# SCH_Satlla_4_Main_Board_2023-01-26.net
KiCad netlist of a schematic drawn in EasyEDA
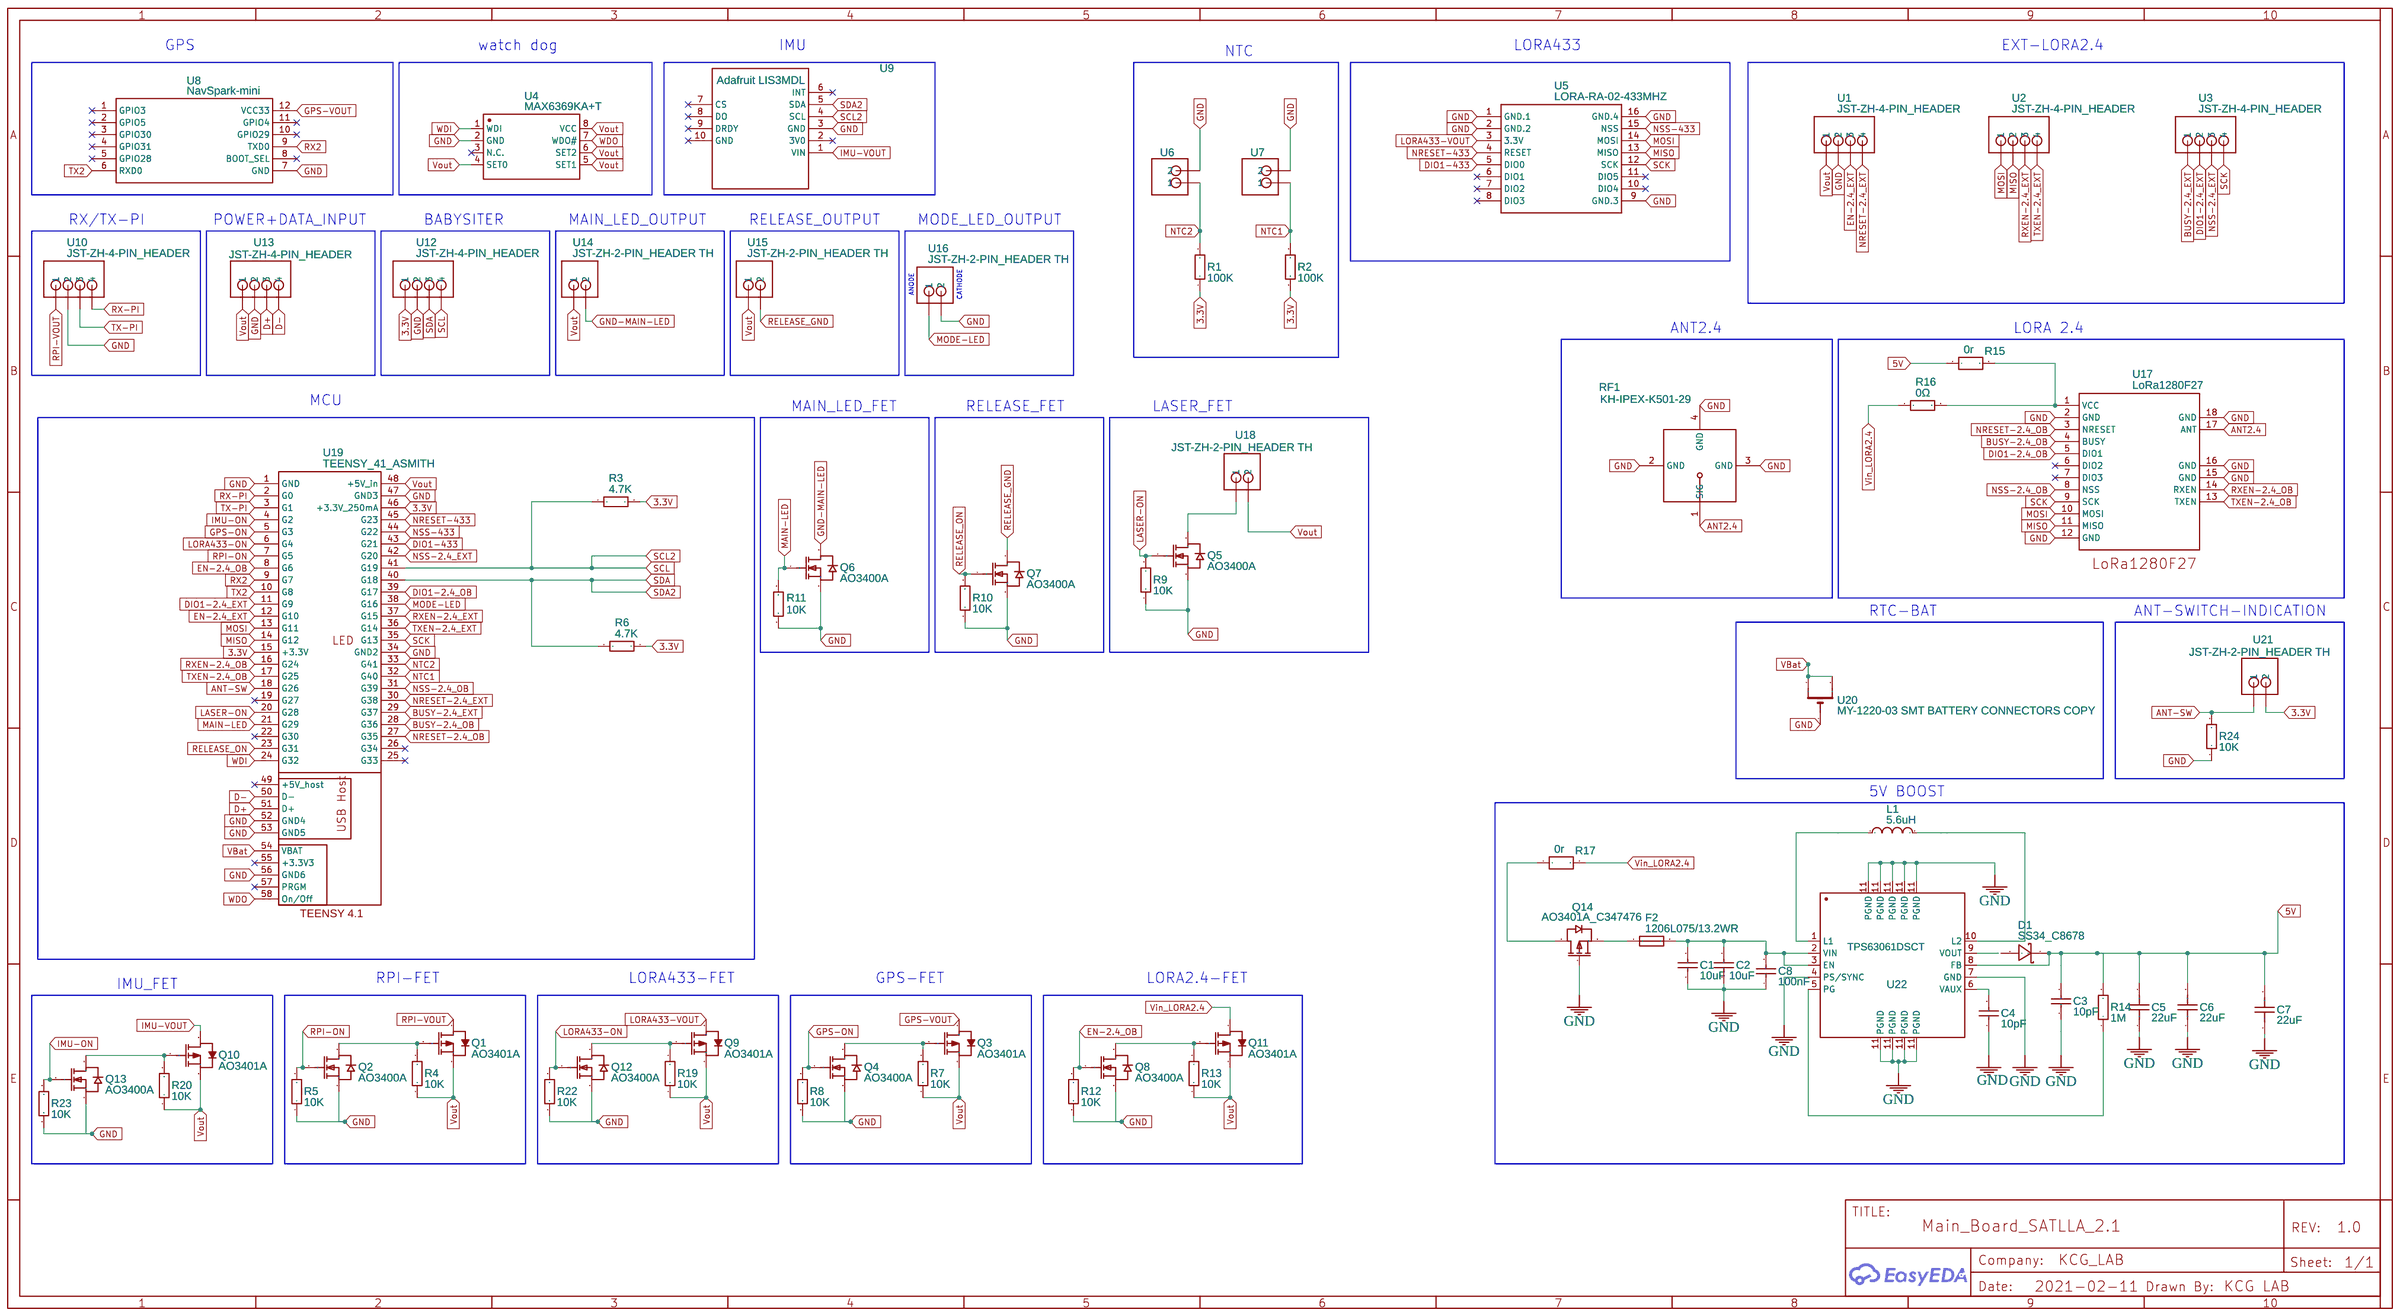
[diagram p0: schematic sheet]

(export (version "E")
  (design (tool "Eeschema 10.0.6"))
  (components
    (comp (ref "C1")
      (value "10uF")
      (fields
        (field (name "BOM_Manufacturer Part") "GRM188R61C106MA73D")
        (field (name "BOM_Supplier Part") "C86277")
      )
      (libsource (lib "") (part "GRM188R61C106MA73D"))
    )
    (comp (ref "C2")
      (value "10uF")
      (fields
        (field (name "BOM_Manufacturer Part") "GRM188R61C106MA73D")
        (field (name "BOM_Supplier Part") "C86277")
      )
      (libsource (lib "") (part "GRM188R61C106MA73D"))
    )
    (comp (ref "C3")
      (value "10pF")
      (fields
        (field (name "BOM_Manufacturer Part") "0603CG100J101NT")
        (field (name "BOM_Supplier Part") "C56033")
      )
      (libsource (lib "") (part "0603CG100J101NT"))
    )
    (comp (ref "C4")
      (value "10pF")
      (fields
        (field (name "BOM_Manufacturer Part") "0603CG100J101NT")
        (field (name "BOM_Supplier Part") "C56033")
      )
      (libsource (lib "") (part "0603CG100J101NT"))
    )
    (comp (ref "C5")
      (value "22uF")
      (fields
        (field (name "BOM_Manufacturer Part") "GRM219R61C226ME15L")
        (field (name "BOM_Supplier Part") "C162295")
      )
      (libsource (lib "") (part "GRM219R61C226ME15L"))
    )
    (comp (ref "C6")
      (value "22uF")
      (fields
        (field (name "BOM_Manufacturer Part") "GRM219R61C226ME15L")
        (field (name "BOM_Supplier Part") "C162295")
      )
      (libsource (lib "") (part "GRM219R61C226ME15L"))
    )
    (comp (ref "C7")
      (value "22uF")
      (fields
        (field (name "BOM_Manufacturer Part") "GRM219R61C226ME15L")
        (field (name "BOM_Supplier Part") "C162295")
      )
      (libsource (lib "") (part "GRM219R61C226ME15L"))
    )
    (comp (ref "C8")
      (value "100nF")
      (fields
        (field (name "BOM_Manufacturer Part") "0603F104M500NT")
        (field (name "BOM_Supplier Part") "C42998")
      )
      (libsource (lib "") (part "0603F104M500NT"))
    )
    (comp (ref "D1")
      (value "SS34_C8678")
      (fields (field (name "BOM_Manufacturer Part") "SS34") (field (name "BOM_Supplier Part") "C8678"))
      (libsource (lib "") (part "SS34_C8678"))
    )
    (comp (ref "F2")
      (value "1206L075/13.2WR")
      (fields (field (name "BOM_Supplier Part") "C207036"))
      (libsource (lib "") (part "1206L075/13.2WR"))
    )
    (comp (ref "L1")
      (value "5.6uH")
      (fields
        (field (name "BOM_Manufacturer Part") "YSPI0530-5R6M")
        (field (name "BOM_Supplier Part") "C497860")
      )
      (libsource (lib "") (part "YSPI0530-5R6M"))
    )
    (comp (ref "Q1")
      (value "AO3401A")
      (fields (field (name "BOM_Supplier Part") "C15127"))
      (libsource (lib "") (part "AO3401A"))
    )
    (comp (ref "Q2")
      (value "AO3400A")
      (fields (field (name "BOM_Supplier Part") "C20917"))
      (libsource (lib "") (part "AO3400A"))
    )
    (comp (ref "Q3")
      (value "AO3401A")
      (fields (field (name "BOM_Supplier Part") "C15127"))
      (libsource (lib "") (part "AO3401A"))
    )
    (comp (ref "Q4")
      (value "AO3400A")
      (fields (field (name "BOM_Supplier Part") "C20917"))
      (libsource (lib "") (part "AO3400A"))
    )
    (comp (ref "Q5")
      (value "AO3400A")
      (fields (field (name "BOM_Supplier Part") "C20917"))
      (libsource (lib "") (part "AO3400A"))
    )
    (comp (ref "Q6")
      (value "AO3400A")
      (fields (field (name "BOM_Supplier Part") "C20917"))
      (libsource (lib "") (part "AO3400A"))
    )
    (comp (ref "Q7")
      (value "AO3400A")
      (fields (field (name "BOM_Supplier Part") "C20917"))
      (libsource (lib "") (part "AO3400A"))
    )
    (comp (ref "Q8")
      (value "AO3400A")
      (fields (field (name "BOM_Supplier Part") "C20917"))
      (libsource (lib "") (part "AO3400A"))
    )
    (comp (ref "Q9")
      (value "AO3401A")
      (fields (field (name "BOM_Supplier Part") "C15127"))
      (libsource (lib "") (part "AO3401A"))
    )
    (comp (ref "Q10")
      (value "AO3401A")
      (fields (field (name "BOM_Supplier Part") "C15127"))
      (libsource (lib "") (part "AO3401A"))
    )
    (comp (ref "Q11")
      (value "AO3401A")
      (fields (field (name "BOM_Supplier Part") "C15127"))
      (libsource (lib "") (part "AO3401A"))
    )
    (comp (ref "Q12")
      (value "AO3400A")
      (fields (field (name "BOM_Supplier Part") "C20917"))
      (libsource (lib "") (part "AO3400A"))
    )
    (comp (ref "Q13")
      (value "AO3400A")
      (fields (field (name "BOM_Supplier Part") "C20917"))
      (libsource (lib "") (part "AO3400A"))
    )
    (comp (ref "Q14")
      (value "AO3401A_C347476")
      (fields (field (name "BOM_Manufacturer Part") "AO3401A") (field (name "BOM_Supplier Part") "C347476"))
      (libsource (lib "") (part "AO3401A_C347476"))
    )
    (comp (ref "R1")
      (value "100K")
      (fields
        (field (name "BOM_Manufacturer Part") "RC0603JR-07100KL")
        (field (name "BOM_Supplier Part") "C100048")
      )
      (libsource (lib "") (part "RC0603JR-07100KL"))
    )
    (comp (ref "R2")
      (value "100K")
      (fields
        (field (name "BOM_Manufacturer Part") "RC0603JR-07100KL")
        (field (name "BOM_Supplier Part") "C100048")
      )
      (libsource (lib "") (part "RC0603JR-07100KL"))
    )
    (comp (ref "R3")
      (value "4.7K")
      (fields
        (field (name "BOM_Manufacturer Part") "RMC06034.7K1%N")
        (field (name "BOM_Supplier Part") "C269713")
      )
      (libsource (lib "") (part "RMC06034.7K1%N"))
    )
    (comp (ref "R4")
      (value "10K")
      (fields
        (field (name "BOM_Manufacturer Part") "0603WAF1002T5E")
        (field (name "BOM_Supplier Part") "C25804")
      )
      (libsource (lib "") (part "0603WAF1002T5E"))
    )
    (comp (ref "R5")
      (value "10K")
      (fields
        (field (name "BOM_Manufacturer Part") "0603WAF1002T5E")
        (field (name "BOM_Supplier Part") "C25804")
      )
      (libsource (lib "") (part "0603WAF1002T5E"))
    )
    (comp (ref "R6")
      (value "4.7K")
      (fields
        (field (name "BOM_Manufacturer Part") "RMC06034.7K1%N")
        (field (name "BOM_Supplier Part") "C269713")
      )
      (libsource (lib "") (part "RMC06034.7K1%N"))
    )
    (comp (ref "R7")
      (value "10K")
      (fields
        (field (name "BOM_Manufacturer Part") "0603WAF1002T5E")
        (field (name "BOM_Supplier Part") "C25804")
      )
      (libsource (lib "") (part "0603WAF1002T5E"))
    )
    (comp (ref "R8")
      (value "10K")
      (fields
        (field (name "BOM_Manufacturer Part") "0603WAF1002T5E")
        (field (name "BOM_Supplier Part") "C25804")
      )
      (libsource (lib "") (part "0603WAF1002T5E"))
    )
    (comp (ref "R9")
      (value "10K")
      (fields
        (field (name "BOM_Manufacturer Part") "0603WAF1002T5E")
        (field (name "BOM_Supplier Part") "C25804")
      )
      (libsource (lib "") (part "0603WAF1002T5E"))
    )
    (comp (ref "R10")
      (value "10K")
      (fields
        (field (name "BOM_Manufacturer Part") "0603WAF1002T5E")
        (field (name "BOM_Supplier Part") "C25804")
      )
      (libsource (lib "") (part "0603WAF1002T5E"))
    )
    (comp (ref "R11")
      (value "10K")
      (fields
        (field (name "BOM_Manufacturer Part") "0603WAF1002T5E")
        (field (name "BOM_Supplier Part") "C25804")
      )
      (libsource (lib "") (part "0603WAF1002T5E"))
    )
    (comp (ref "R12")
      (value "10K")
      (fields
        (field (name "BOM_Manufacturer Part") "0603WAF1002T5E")
        (field (name "BOM_Supplier Part") "C25804")
      )
      (libsource (lib "") (part "0603WAF1002T5E"))
    )
    (comp (ref "R13")
      (value "10K")
      (fields
        (field (name "BOM_Manufacturer Part") "0603WAF1002T5E")
        (field (name "BOM_Supplier Part") "C25804")
      )
      (libsource (lib "") (part "0603WAF1002T5E"))
    )
    (comp (ref "R14")
      (value "1M")
      (fields
        (field (name "BOM_Manufacturer Part") "ERJ3GEYJ105V")
        (field (name "BOM_Supplier Part") "C278634")
      )
      (libsource (lib "") (part "ERJ3GEYJ105V"))
    )
    (comp (ref "R15") (value "0r") (libsource (lib "") (part "R_0603_EU")))
    (comp (ref "R16")
      (value "0Ω")
      (fields
        (field (name "BOM_Manufacturer Part") "0603WAF0000T5E")
        (field (name "BOM_Supplier Part") "C21189")
      )
      (libsource (lib "") (part "0603WAF0000T5E"))
    )
    (comp (ref "R17") (value "0r") (libsource (lib "") (part "R_0603_EU")))
    (comp (ref "R19")
      (value "10K")
      (fields
        (field (name "BOM_Manufacturer Part") "0603WAF1002T5E")
        (field (name "BOM_Supplier Part") "C25804")
      )
      (libsource (lib "") (part "0603WAF1002T5E"))
    )
    (comp (ref "R20")
      (value "10K")
      (fields
        (field (name "BOM_Manufacturer Part") "0603WAF1002T5E")
        (field (name "BOM_Supplier Part") "C25804")
      )
      (libsource (lib "") (part "0603WAF1002T5E"))
    )
    (comp (ref "R22")
      (value "10K")
      (fields
        (field (name "BOM_Manufacturer Part") "0603WAF1002T5E")
        (field (name "BOM_Supplier Part") "C25804")
      )
      (libsource (lib "") (part "0603WAF1002T5E"))
    )
    (comp (ref "R23")
      (value "10K")
      (fields
        (field (name "BOM_Manufacturer Part") "0603WAF1002T5E")
        (field (name "BOM_Supplier Part") "C25804")
      )
      (libsource (lib "") (part "0603WAF1002T5E"))
    )
    (comp (ref "R24")
      (value "10K")
      (fields
        (field (name "BOM_Manufacturer Part") "0603WAF1002T5E")
        (field (name "BOM_Supplier Part") "C25804")
      )
      (libsource (lib "") (part "0603WAF1002T5E"))
    )
    (comp (ref "RF1")
      (value "KH-IPEX-K501-29")
      (fields (field (name "BOM_Supplier Part") "C411563"))
      (libsource (lib "") (part "KH-IPEX-K501-29"))
    )
    (comp (ref "U1") (value "JST-ZH-4-PIN_HEADER") (libsource (lib "") (part "JST-ZH-4-PIN_HEADER")))
    (comp (ref "U2") (value "JST-ZH-4-PIN_HEADER") (libsource (lib "") (part "JST-ZH-4-PIN_HEADER")))
    (comp (ref "U3") (value "JST-ZH-4-PIN_HEADER") (libsource (lib "") (part "JST-ZH-4-PIN_HEADER")))
    (comp (ref "U4")
      (value "MAX6369KA+T")
      (fields (field (name "BOM_Supplier Part") "C128613"))
      (libsource (lib "") (part "MAX6369KA+T"))
    )
    (comp (ref "U5") (value "LORA-RA-02-433MHZ") (libsource (lib "") (part "LORA-RA-02-433MHZ")))
    (comp (ref "U6") (value "JST-ZH-2-PIN_HEADER TH") (libsource (lib "") (part "JST-ZH-2-PIN_HEADER TH_1")))
    (comp (ref "U7") (value "JST-ZH-2-PIN_HEADER TH") (libsource (lib "") (part "JST-ZH-2-PIN_HEADER TH_1")))
    (comp (ref "U8") (value "NavSpark-mini") (libsource (lib "") (part "NavSpark-mini")))
    (comp (ref "U9")
      (value "Adafruit LIS3MDL")
      (fields (field (name "BOM_Supplier Part") "485-4479"))
      (libsource (lib "") (part "Adafruit LIS3MDL"))
    )
    (comp (ref "U10") (value "JST-ZH-4-PIN_HEADER") (libsource (lib "") (part "JST-ZH-4-PIN_HEADER")))
    (comp (ref "U12") (value "JST-ZH-4-PIN_HEADER") (libsource (lib "") (part "JST-ZH-4-PIN_HEADER")))
    (comp (ref "U13") (value "JST-ZH-4-PIN_HEADER") (libsource (lib "") (part "JST-ZH-4-PIN_HEADER")))
    (comp (ref "U14") (value "JST-ZH-2-PIN_HEADER TH") (libsource (lib "") (part "JST-ZH-2-PIN_HEADER TH")))
    (comp (ref "U15") (value "JST-ZH-2-PIN_HEADER TH") (libsource (lib "") (part "JST-ZH-2-PIN_HEADER TH")))
    (comp (ref "U16") (value "JST-ZH-2-PIN_HEADER TH") (libsource (lib "") (part "JST-ZH-2-PIN_HEADER TH")))
    (comp (ref "U17") (value "LoRa1280F27") (libsource (lib "") (part "LoRa1280F27")))
    (comp (ref "U18") (value "JST-ZH-2-PIN_HEADER TH") (libsource (lib "") (part "JST-ZH-2-PIN_HEADER TH")))
    (comp (ref "U19") (value "TEENSY_41_ASMITH") (libsource (lib "") (part "TEENSY_41_ASMITH")))
    (comp (ref "U20")
      (value "MY-1220-03 SMT BATTERY CONNECTORS COPY")
      (libsource (lib "") (part "MY-1220-03 SMT BATTERY CONNECTORS COPY"))
    )
    (comp (ref "U21") (value "JST-ZH-2-PIN_HEADER TH") (libsource (lib "") (part "JST-ZH-2-PIN_HEADER TH")))
    (comp (ref "U22")
      (value "TPS63061DSCT")
      (fields (field (name "BOM_Supplier Part") "C134127"))
      (libsource (lib "") (part "TPS63061DSCT"))
    )
  )
  (nets
    (net (code "1") (name "3.3V") (class "Default")
      (node (ref "R1") (pin "1") (pinfunction "1_1") (pintype "unspecified"))
      (node (ref "R2") (pin "1") (pinfunction "1_1") (pintype "unspecified"))
      (node (ref "R3") (pin "2") (pinfunction "2_2") (pintype "unspecified"))
      (node (ref "R6") (pin "2") (pinfunction "2_2") (pintype "unspecified"))
      (node (ref "U12") (pin "P1") (pinfunction "1_P1") (pintype "unspecified"))
      (node (ref "U19") (pin "15") (pinfunction "+3.3V_15") (pintype "unspecified"))
      (node (ref "U19") (pin "46") (pinfunction "+3.3V_250mA_46") (pintype "unspecified"))
      (node (ref "U21") (pin "2") (pinfunction "2_2") (pintype "unspecified"))
    )
    (net (code "2") (name "5V") (class "Default")
      (node (ref "C3") (pin "2") (pinfunction "2_2") (pintype "input"))
      (node (ref "C5") (pin "2") (pinfunction "2_2") (pintype "unspecified"))
      (node (ref "C6") (pin "2") (pinfunction "2_2") (pintype "unspecified"))
      (node (ref "C7") (pin "2") (pinfunction "2_2") (pintype "unspecified"))
      (node (ref "D1") (pin "1") (pinfunction "K_1") (pintype "unspecified"))
      (node (ref "R14") (pin "2") (pinfunction "2_2") (pintype "unspecified"))
      (node (ref "R15") (pin "1") (pinfunction "1_1") (pintype "unspecified"))
      (node (ref "U22") (pin "8") (pinfunction "FB_8") (pintype "unspecified"))
    )
    (net (code "3") (name "ANT-SW") (class "Default")
      (node (ref "R24") (pin "2") (pinfunction "2_2") (pintype "input"))
      (node (ref "U19") (pin "18") (pinfunction "G26_18") (pintype "unspecified"))
      (node (ref "U21") (pin "1") (pinfunction "1_1") (pintype "unspecified"))
    )
    (net (code "4") (name "ANT2.4") (class "Default")
      (node (ref "RF1") (pin "1") (pinfunction "SIG_1") (pintype "unspecified"))
      (node (ref "U17") (pin "17") (pinfunction "ANT_17") (pintype "unspecified"))
    )
    (net (code "5") (name "BUSY-2.4_EXT") (class "Default")
      (node (ref "U19") (pin "29") (pinfunction "G37_29") (pintype "unspecified"))
      (node (ref "U3") (pin "P1") (pinfunction "1_P1") (pintype "unspecified"))
    )
    (net (code "6") (name "BUSY-2.4_OB") (class "Default")
      (node (ref "U17") (pin "4") (pinfunction "BUSY_4") (pintype "unspecified"))
      (node (ref "U19") (pin "28") (pinfunction "G36_28") (pintype "unspecified"))
    )
    (net (code "7") (name "D+") (class "Default")
      (node (ref "U13") (pin "P3") (pinfunction "3_P3") (pintype "unspecified"))
      (node (ref "U19") (pin "51") (pinfunction "D+_51") (pintype "unspecified"))
    )
    (net (code "8") (name "D-") (class "Default")
      (node (ref "U13") (pin "P4") (pinfunction "4_P4") (pintype "unspecified"))
      (node (ref "U19") (pin "50") (pinfunction "D-_50") (pintype "unspecified"))
    )
    (net (code "9") (name "DIO1-2.4_EXT") (class "Default")
      (node (ref "U19") (pin "11") (pinfunction "G9_11") (pintype "unspecified"))
      (node (ref "U3") (pin "P2") (pinfunction "2_P2") (pintype "unspecified"))
    )
    (net (code "10") (name "DIO1-2.4_OB") (class "Default")
      (node (ref "U17") (pin "5") (pinfunction "DIO1_5") (pintype "unspecified"))
      (node (ref "U19") (pin "39") (pinfunction "G17_39") (pintype "unspecified"))
    )
    (net (code "11") (name "DIO1-433") (class "Default")
      (node (ref "U19") (pin "43") (pinfunction "G21_43") (pintype "unspecified"))
      (node (ref "U5") (pin "5") (pinfunction "DIO0_5") (pintype "unspecified"))
    )
    (net (code "12") (name "EN-2.4_EXT") (class "Default")
      (node (ref "U1") (pin "P3") (pinfunction "3_P3") (pintype "unspecified"))
      (node (ref "U19") (pin "12") (pinfunction "G10_12") (pintype "unspecified"))
    )
    (net (code "13") (name "EN-2.4_OB") (class "Default")
      (node (ref "Q8") (pin "1") (pinfunction "G_1") (pintype "unspecified"))
      (node (ref "R12") (pin "2") (pinfunction "2_2") (pintype "input"))
      (node (ref "U19") (pin "8") (pinfunction "G6_8") (pintype "unspecified"))
    )
    (net (code "14") (name "GND") (class "Default")
      (node (ref "C1") (pin "1") (pinfunction "1_1") (pintype "input"))
      (node (ref "C2") (pin "1") (pinfunction "1_1") (pintype "input"))
      (node (ref "C3") (pin "1") (pinfunction "1_1") (pintype "input"))
      (node (ref "C4") (pin "1") (pinfunction "1_1") (pintype "input"))
      (node (ref "C5") (pin "1") (pinfunction "1_1") (pintype "unspecified"))
      (node (ref "C6") (pin "1") (pinfunction "1_1") (pintype "unspecified"))
      (node (ref "C7") (pin "1") (pinfunction "1_1") (pintype "unspecified"))
      (node (ref "C8") (pin "1") (pinfunction "1_1") (pintype "input"))
      (node (ref "Q12") (pin "2") (pinfunction "S_2") (pintype "unspecified"))
      (node (ref "Q13") (pin "2") (pinfunction "S_2") (pintype "unspecified"))
      (node (ref "Q14") (pin "1") (pinfunction "G_1") (pintype "unspecified"))
      (node (ref "Q2") (pin "2") (pinfunction "S_2") (pintype "unspecified"))
      (node (ref "Q4") (pin "2") (pinfunction "S_2") (pintype "unspecified"))
      (node (ref "Q5") (pin "2") (pinfunction "S_2") (pintype "unspecified"))
      (node (ref "Q6") (pin "2") (pinfunction "S_2") (pintype "unspecified"))
      (node (ref "Q7") (pin "2") (pinfunction "S_2") (pintype "unspecified"))
      (node (ref "Q8") (pin "2") (pinfunction "S_2") (pintype "unspecified"))
      (node (ref "R10") (pin "1") (pinfunction "1_1") (pintype "input"))
      (node (ref "R11") (pin "1") (pinfunction "1_1") (pintype "input"))
      (node (ref "R12") (pin "1") (pinfunction "1_1") (pintype "input"))
      (node (ref "R22") (pin "1") (pinfunction "1_1") (pintype "input"))
      (node (ref "R23") (pin "1") (pinfunction "1_1") (pintype "input"))
      (node (ref "R24") (pin "1") (pinfunction "1_1") (pintype "input"))
      (node (ref "R5") (pin "1") (pinfunction "1_1") (pintype "input"))
      (node (ref "R8") (pin "1") (pinfunction "1_1") (pintype "input"))
      (node (ref "R9") (pin "1") (pinfunction "1_1") (pintype "input"))
      (node (ref "RF1") (pin "2") (pinfunction "GND_2") (pintype "unspecified"))
      (node (ref "RF1") (pin "3") (pinfunction "GND_3") (pintype "unspecified"))
      (node (ref "RF1") (pin "4") (pinfunction "GND_4") (pintype "unspecified"))
      (node (ref "U1") (pin "P2") (pinfunction "2_P2") (pintype "unspecified"))
      (node (ref "U10") (pin "P2") (pinfunction "2_P2") (pintype "unspecified"))
      (node (ref "U12") (pin "P2") (pinfunction "2_P2") (pintype "unspecified"))
      (node (ref "U13") (pin "P2") (pinfunction "2_P2") (pintype "unspecified"))
      (node (ref "U16") (pin "2") (pinfunction "2_2") (pintype "unspecified"))
      (node (ref "U17") (pin "12") (pinfunction "GND_12") (pintype "unspecified"))
      (node (ref "U17") (pin "15") (pinfunction "GND_15") (pintype "unspecified"))
      (node (ref "U17") (pin "16") (pinfunction "GND_16") (pintype "unspecified"))
      (node (ref "U17") (pin "18") (pinfunction "GND_18") (pintype "unspecified"))
      (node (ref "U17") (pin "2") (pinfunction "GND_2") (pintype "unspecified"))
      (node (ref "U19") (pin "1") (pinfunction "GND_1") (pintype "unspecified"))
      (node (ref "U19") (pin "34") (pinfunction "GND2_34") (pintype "unspecified"))
      (node (ref "U19") (pin "47") (pinfunction "GND3_47") (pintype "unspecified"))
      (node (ref "U19") (pin "52") (pinfunction "GND4_52") (pintype "unspecified"))
      (node (ref "U19") (pin "53") (pinfunction "GND5_53") (pintype "unspecified"))
      (node (ref "U19") (pin "56") (pinfunction "GND6_56") (pintype "unspecified"))
      (node (ref "U20") (pin "4") (pinfunction "-_4") (pintype "unspecified"))
      (node (ref "U22") (pin "11") (pinfunction "PGND_11") (pintype "unspecified"))
      (node (ref "U22") (pin "4") (pinfunction "PS/SYNC_4") (pintype "unspecified"))
      (node (ref "U22") (pin "7") (pinfunction "GND_7") (pintype "unspecified"))
      (node (ref "U4") (pin "2") (pinfunction "GND_2") (pintype "unspecified"))
      (node (ref "U5") (pin "1") (pinfunction "GND.1_1") (pintype "passive"))
      (node (ref "U5") (pin "16") (pinfunction "GND.4_16") (pintype "passive"))
      (node (ref "U5") (pin "2") (pinfunction "GND.2_2") (pintype "passive"))
      (node (ref "U5") (pin "9") (pinfunction "GND.3_9") (pintype "passive"))
      (node (ref "U6") (pin "2") (pinfunction "2_2") (pintype "unspecified"))
      (node (ref "U7") (pin "2") (pinfunction "2_2") (pintype "unspecified"))
      (node (ref "U8") (pin "7") (pinfunction "GND_7") (pintype "unspecified"))
      (node (ref "U9") (pin "3") (pinfunction "GND_3") (pintype "passive"))
    )
    (net (code "15") (name "GND-MAIN-LED") (class "Default")
      (node (ref "Q6") (pin "3") (pinfunction "D_3") (pintype "unspecified"))
      (node (ref "U14") (pin "2") (pinfunction "2_2") (pintype "unspecified"))
    )
    (net (code "16") (name "GPS-ON") (class "Default")
      (node (ref "Q4") (pin "1") (pinfunction "G_1") (pintype "unspecified"))
      (node (ref "R8") (pin "2") (pinfunction "2_2") (pintype "input"))
      (node (ref "U19") (pin "5") (pinfunction "G3_5") (pintype "unspecified"))
    )
    (net (code "17") (name "GPS-VOUT") (class "Default")
      (node (ref "Q3") (pin "3") (pinfunction "D_3") (pintype "unspecified"))
      (node (ref "U8") (pin "12") (pinfunction "VCC33_12") (pintype "unspecified"))
    )
    (net (code "18") (name "IMU-ON") (class "Default")
      (node (ref "Q13") (pin "1") (pinfunction "G_1") (pintype "unspecified"))
      (node (ref "R23") (pin "2") (pinfunction "2_2") (pintype "input"))
      (node (ref "U19") (pin "4") (pinfunction "G2_4") (pintype "unspecified"))
    )
    (net (code "19") (name "IMU-VOUT") (class "Default")
      (node (ref "Q10") (pin "3") (pinfunction "D_3") (pintype "unspecified"))
      (node (ref "U9") (pin "1") (pinfunction "VIN_1") (pintype "passive"))
    )
    (net (code "20") (name "LASER-ON") (class "Default")
      (node (ref "Q5") (pin "1") (pinfunction "G_1") (pintype "unspecified"))
      (node (ref "R9") (pin "2") (pinfunction "2_2") (pintype "input"))
      (node (ref "U19") (pin "20") (pinfunction "G28_20") (pintype "unspecified"))
    )
    (net (code "21") (name "LORA433-ON") (class "Default")
      (node (ref "Q12") (pin "1") (pinfunction "G_1") (pintype "unspecified"))
      (node (ref "R22") (pin "2") (pinfunction "2_2") (pintype "input"))
      (node (ref "U19") (pin "6") (pinfunction "G4_6") (pintype "unspecified"))
    )
    (net (code "22") (name "LORA433-VOUT") (class "Default")
      (node (ref "Q9") (pin "3") (pinfunction "D_3") (pintype "unspecified"))
      (node (ref "U5") (pin "3") (pinfunction "3.3V_3") (pintype "passive"))
    )
    (net (code "23") (name "MAIN-LED") (class "Default")
      (node (ref "Q6") (pin "1") (pinfunction "G_1") (pintype "unspecified"))
      (node (ref "R11") (pin "2") (pinfunction "2_2") (pintype "input"))
      (node (ref "U19") (pin "21") (pinfunction "G29_21") (pintype "unspecified"))
    )
    (net (code "24") (name "MISO") (class "Default")
      (node (ref "U17") (pin "11") (pinfunction "MISO_11") (pintype "unspecified"))
      (node (ref "U19") (pin "14") (pinfunction "G12_14") (pintype "unspecified"))
      (node (ref "U2") (pin "P2") (pinfunction "2_P2") (pintype "unspecified"))
      (node (ref "U5") (pin "13") (pinfunction "MISO_13") (pintype "unspecified"))
    )
    (net (code "25") (name "MODE-LED") (class "Default")
      (node (ref "U16") (pin "1") (pinfunction "1_1") (pintype "unspecified"))
      (node (ref "U19") (pin "38") (pinfunction "G16_38") (pintype "unspecified"))
    )
    (net (code "26") (name "MOSI") (class "Default")
      (node (ref "U17") (pin "10") (pinfunction "MOSI_10") (pintype "unspecified"))
      (node (ref "U19") (pin "13") (pinfunction "G11_13") (pintype "unspecified"))
      (node (ref "U2") (pin "P1") (pinfunction "1_P1") (pintype "unspecified"))
      (node (ref "U5") (pin "14") (pinfunction "MOSI_14") (pintype "unspecified"))
    )
    (net (code "27") (name "NRESET-2.4_EXT") (class "Default")
      (node (ref "U1") (pin "P4") (pinfunction "4_P4") (pintype "unspecified"))
      (node (ref "U19") (pin "30") (pinfunction "G38_30") (pintype "unspecified"))
    )
    (net (code "28") (name "NRESET-2.4_OB") (class "Default")
      (node (ref "U17") (pin "3") (pinfunction "NRESET_3") (pintype "unspecified"))
      (node (ref "U19") (pin "27") (pinfunction "G35_27") (pintype "unspecified"))
    )
    (net (code "29") (name "NRESET-433") (class "Default")
      (node (ref "U19") (pin "45") (pinfunction "G23_45") (pintype "unspecified"))
      (node (ref "U5") (pin "4") (pinfunction "RESET_4") (pintype "unspecified"))
    )
    (net (code "30") (name "NSS-2.4_EXT") (class "Default")
      (node (ref "U19") (pin "42") (pinfunction "G20_42") (pintype "unspecified"))
      (node (ref "U3") (pin "P3") (pinfunction "3_P3") (pintype "unspecified"))
    )
    (net (code "31") (name "NSS-2.4_OB") (class "Default")
      (node (ref "U17") (pin "8") (pinfunction "NSS_8") (pintype "unspecified"))
      (node (ref "U19") (pin "31") (pinfunction "G39_31") (pintype "unspecified"))
    )
    (net (code "32") (name "NSS-433") (class "Default")
      (node (ref "U19") (pin "44") (pinfunction "G22_44") (pintype "unspecified"))
      (node (ref "U5") (pin "15") (pinfunction "NSS_15") (pintype "unspecified"))
    )
    (net (code "33") (name "NTC1") (class "Default")
      (node (ref "R2") (pin "2") (pinfunction "2_2") (pintype "unspecified"))
      (node (ref "U19") (pin "32") (pinfunction "G40_32") (pintype "unspecified"))
      (node (ref "U7") (pin "1") (pinfunction "1_1") (pintype "unspecified"))
    )
    (net (code "34") (name "NTC2") (class "Default")
      (node (ref "R1") (pin "2") (pinfunction "2_2") (pintype "unspecified"))
      (node (ref "U19") (pin "33") (pinfunction "G41_33") (pintype "unspecified"))
      (node (ref "U6") (pin "1") (pinfunction "1_1") (pintype "unspecified"))
    )
    (net (code "35") (name "Net-(Q1-G)") (class "Default")
      (node (ref "Q1") (pin "1") (pinfunction "G_1") (pintype "unspecified"))
      (node (ref "Q2") (pin "3") (pinfunction "D_3") (pintype "unspecified"))
      (node (ref "R4") (pin "2") (pinfunction "2_2") (pintype "input"))
    )
    (net (code "36") (name "Net-(Q3-G)") (class "Default")
      (node (ref "Q3") (pin "1") (pinfunction "G_1") (pintype "unspecified"))
      (node (ref "Q4") (pin "3") (pinfunction "D_3") (pintype "unspecified"))
      (node (ref "R7") (pin "2") (pinfunction "2_2") (pintype "input"))
    )
    (net (code "37") (name "Net-(Q5-D)") (class "Default")
      (node (ref "Q5") (pin "3") (pinfunction "D_3") (pintype "unspecified"))
      (node (ref "U18") (pin "1") (pinfunction "1_1") (pintype "unspecified"))
    )
    (net (code "38") (name "Net-(Q10-G)") (class "Default")
      (node (ref "Q10") (pin "1") (pinfunction "G_1") (pintype "unspecified"))
      (node (ref "Q13") (pin "3") (pinfunction "D_3") (pintype "unspecified"))
      (node (ref "R20") (pin "2") (pinfunction "2_2") (pintype "input"))
    )
    (net (code "39") (name "Net-(Q11-G)") (class "Default")
      (node (ref "Q11") (pin "1") (pinfunction "G_1") (pintype "unspecified"))
      (node (ref "Q8") (pin "3") (pinfunction "D_3") (pintype "unspecified"))
      (node (ref "R13") (pin "2") (pinfunction "2_2") (pintype "input"))
    )
    (net (code "40") (name "Net-(Q12-D)") (class "Default")
      (node (ref "Q12") (pin "3") (pinfunction "D_3") (pintype "unspecified"))
      (node (ref "Q9") (pin "1") (pinfunction "G_1") (pintype "unspecified"))
      (node (ref "R19") (pin "2") (pinfunction "2_2") (pintype "input"))
    )
    (net (code "41") (name "Net-(Q14-D)") (class "Default")
      (node (ref "Q14") (pin "3") (pinfunction "D_3") (pintype "unspecified"))
      (node (ref "R17") (pin "1") (pinfunction "1_1") (pintype "unspecified"))
    )
    (net (code "42") (name "Net-(Q14-S)") (class "Default")
      (node (ref "F2") (pin "1") (pinfunction "1_1") (pintype "unspecified"))
      (node (ref "Q14") (pin "2") (pinfunction "S_2") (pintype "unspecified"))
    )
    (net (code "43") (name "Net-(U17-VCC)") (class "Default")
      (node (ref "R15") (pin "2") (pinfunction "2_2") (pintype "unspecified"))
      (node (ref "R16") (pin "2") (pinfunction "2_2") (pintype "input"))
      (node (ref "U17") (pin "1") (pinfunction "VCC_1") (pintype "unspecified"))
    )
    (net (code "44") (name "Net-(U22-EN)") (class "Default")
      (node (ref "C1") (pin "2") (pinfunction "2_2") (pintype "input"))
      (node (ref "C2") (pin "2") (pinfunction "2_2") (pintype "input"))
      (node (ref "C8") (pin "2") (pinfunction "2_2") (pintype "input"))
      (node (ref "F2") (pin "2") (pinfunction "2_2") (pintype "unspecified"))
      (node (ref "U22") (pin "2") (pinfunction "VIN_2") (pintype "unspecified"))
      (node (ref "U22") (pin "3") (pinfunction "EN_3") (pintype "unspecified"))
    )
    (net (code "45") (name "Net-(U22-L1)") (class "Default")
      (node (ref "L1") (pin "1") (pinfunction "1_1") (pintype "unspecified"))
      (node (ref "U22") (pin "1") (pinfunction "L1_1") (pintype "unspecified"))
    )
    (net (code "46") (name "Net-(U22-L2)") (class "Default")
      (node (ref "L1") (pin "2") (pinfunction "2_2") (pintype "unspecified"))
      (node (ref "U22") (pin "10") (pinfunction "L2_10") (pintype "unspecified"))
    )
    (net (code "47") (name "Net-(U22-PG)") (class "Default")
      (node (ref "R14") (pin "1") (pinfunction "1_1") (pintype "unspecified"))
      (node (ref "U22") (pin "5") (pinfunction "PG_5") (pintype "unspecified"))
    )
    (net (code "48") (name "Net-(U22-VAUX)") (class "Default")
      (node (ref "C4") (pin "2") (pinfunction "2_2") (pintype "input"))
      (node (ref "U22") (pin "6") (pinfunction "VAUX_6") (pintype "unspecified"))
    )
    (net (code "49") (name "RELEASE_GND") (class "Default")
      (node (ref "Q7") (pin "3") (pinfunction "D_3") (pintype "unspecified"))
      (node (ref "U15") (pin "2") (pinfunction "2_2") (pintype "unspecified"))
    )
    (net (code "50") (name "RELEASE_ON") (class "Default")
      (node (ref "Q7") (pin "1") (pinfunction "G_1") (pintype "unspecified"))
      (node (ref "R10") (pin "2") (pinfunction "2_2") (pintype "input"))
      (node (ref "U19") (pin "23") (pinfunction "G31_23") (pintype "unspecified"))
    )
    (net (code "51") (name "RPI-ON") (class "Default")
      (node (ref "Q2") (pin "1") (pinfunction "G_1") (pintype "unspecified"))
      (node (ref "R5") (pin "2") (pinfunction "2_2") (pintype "input"))
      (node (ref "U19") (pin "7") (pinfunction "G5_7") (pintype "unspecified"))
    )
    (net (code "52") (name "RPI-VOUT") (class "Default")
      (node (ref "Q1") (pin "3") (pinfunction "D_3") (pintype "unspecified"))
      (node (ref "U10") (pin "P1") (pinfunction "1_P1") (pintype "unspecified"))
    )
    (net (code "53") (name "RX-PI") (class "Default")
      (node (ref "U10") (pin "P4") (pinfunction "4_P4") (pintype "unspecified"))
      (node (ref "U19") (pin "2") (pinfunction "G0_2") (pintype "unspecified"))
    )
    (net (code "54") (name "RX2") (class "Default")
      (node (ref "U19") (pin "9") (pinfunction "G7_9") (pintype "unspecified"))
      (node (ref "U8") (pin "9") (pinfunction "TXD0_9") (pintype "unspecified"))
    )
    (net (code "55") (name "RXEN-2.4_EXT") (class "Default")
      (node (ref "U19") (pin "37") (pinfunction "G15_37") (pintype "unspecified"))
      (node (ref "U2") (pin "P3") (pinfunction "3_P3") (pintype "unspecified"))
    )
    (net (code "56") (name "RXEN-2.4_OB") (class "Default")
      (node (ref "U17") (pin "14") (pinfunction "RXEN_14") (pintype "unspecified"))
      (node (ref "U19") (pin "16") (pinfunction "G24_16") (pintype "unspecified"))
    )
    (net (code "57") (name "SCK") (class "Default")
      (node (ref "U17") (pin "9") (pinfunction "SCK_9") (pintype "unspecified"))
      (node (ref "U19") (pin "35") (pinfunction "G13_35") (pintype "unspecified"))
      (node (ref "U3") (pin "P4") (pinfunction "4_P4") (pintype "unspecified"))
      (node (ref "U5") (pin "12") (pinfunction "SCK_12") (pintype "unspecified"))
    )
    (net (code "58") (name "SCL") (class "Default")
      (node (ref "R3") (pin "1") (pinfunction "1_1") (pintype "unspecified"))
      (node (ref "U12") (pin "P4") (pinfunction "4_P4") (pintype "unspecified"))
      (node (ref "U19") (pin "41") (pinfunction "G19_41") (pintype "unspecified"))
      (node (ref "U9") (pin "4") (pinfunction "SCL_4") (pintype "bidirectional"))
    )
    (net (code "59") (name "SDA") (class "Default")
      (node (ref "R6") (pin "1") (pinfunction "1_1") (pintype "unspecified"))
      (node (ref "U12") (pin "P3") (pinfunction "3_P3") (pintype "unspecified"))
      (node (ref "U19") (pin "40") (pinfunction "G18_40") (pintype "unspecified"))
      (node (ref "U9") (pin "5") (pinfunction "SDA_5") (pintype "bidirectional"))
    )
    (net (code "60") (name "TX-PI") (class "Default")
      (node (ref "U10") (pin "P3") (pinfunction "3_P3") (pintype "unspecified"))
      (node (ref "U19") (pin "3") (pinfunction "G1_3") (pintype "unspecified"))
    )
    (net (code "61") (name "TX2") (class "Default")
      (node (ref "U19") (pin "10") (pinfunction "G8_10") (pintype "unspecified"))
      (node (ref "U8") (pin "6") (pinfunction "RXD0_6") (pintype "unspecified"))
    )
    (net (code "62") (name "TXEN-2.4_EXT") (class "Default")
      (node (ref "U19") (pin "36") (pinfunction "G14_36") (pintype "unspecified"))
      (node (ref "U2") (pin "P4") (pinfunction "4_P4") (pintype "unspecified"))
    )
    (net (code "63") (name "TXEN-2.4_OB") (class "Default")
      (node (ref "U17") (pin "13") (pinfunction "TXEN_13") (pintype "unspecified"))
      (node (ref "U19") (pin "17") (pinfunction "G25_17") (pintype "unspecified"))
    )
    (net (code "64") (name "VBat") (class "Default")
      (node (ref "U19") (pin "54") (pinfunction "VBAT_54") (pintype "unspecified"))
      (node (ref "U20") (pin "1") (pinfunction "+_1") (pintype "unspecified"))
      (node (ref "U20") (pin "2") (pinfunction "+_2") (pintype "unspecified"))
    )
    (net (code "65") (name "Vin_LORA2.4") (class "Default")
      (node (ref "Q11") (pin "3") (pinfunction "D_3") (pintype "unspecified"))
      (node (ref "R16") (pin "1") (pinfunction "1_1") (pintype "input"))
      (node (ref "R17") (pin "2") (pinfunction "2_2") (pintype "unspecified"))
    )
    (net (code "66") (name "Vout") (class "Default")
      (node (ref "Q1") (pin "2") (pinfunction "S_2") (pintype "unspecified"))
      (node (ref "Q10") (pin "2") (pinfunction "S_2") (pintype "unspecified"))
      (node (ref "Q11") (pin "2") (pinfunction "S_2") (pintype "unspecified"))
      (node (ref "Q3") (pin "2") (pinfunction "S_2") (pintype "unspecified"))
      (node (ref "Q9") (pin "2") (pinfunction "S_2") (pintype "unspecified"))
      (node (ref "R13") (pin "1") (pinfunction "1_1") (pintype "input"))
      (node (ref "R19") (pin "1") (pinfunction "1_1") (pintype "input"))
      (node (ref "R20") (pin "1") (pinfunction "1_1") (pintype "input"))
      (node (ref "R4") (pin "1") (pinfunction "1_1") (pintype "input"))
      (node (ref "R7") (pin "1") (pinfunction "1_1") (pintype "input"))
      (node (ref "U1") (pin "P1") (pinfunction "1_P1") (pintype "unspecified"))
      (node (ref "U13") (pin "P1") (pinfunction "1_P1") (pintype "unspecified"))
      (node (ref "U14") (pin "1") (pinfunction "1_1") (pintype "unspecified"))
      (node (ref "U15") (pin "1") (pinfunction "1_1") (pintype "unspecified"))
      (node (ref "U18") (pin "2") (pinfunction "2_2") (pintype "unspecified"))
      (node (ref "U19") (pin "48") (pinfunction "+5V_in_48") (pintype "unspecified"))
      (node (ref "U4") (pin "4") (pinfunction "SET0_4") (pintype "unspecified"))
      (node (ref "U4") (pin "5") (pinfunction "SET1_5") (pintype "unspecified"))
      (node (ref "U4") (pin "6") (pinfunction "SET2_6") (pintype "unspecified"))
      (node (ref "U4") (pin "8") (pinfunction "VCC_8") (pintype "unspecified"))
    )
    (net (code "67") (name "WDI") (class "Default")
      (node (ref "U19") (pin "24") (pinfunction "G32_24") (pintype "unspecified"))
      (node (ref "U4") (pin "1") (pinfunction "WDI_1") (pintype "unspecified"))
    )
    (net (code "68") (name "WDO") (class "Default")
      (node (ref "U19") (pin "58") (pinfunction "On/Off_58") (pintype "unspecified"))
      (node (ref "U4") (pin "7") (pinfunction "WDO#_7") (pintype "unspecified"))
    )
    (net (code "69") (name "unconnected-(D1-A-Pad2)") (class "Default")
      (node (ref "D1") (pin "2") (pinfunction "A_2") (pintype "unspecified"))
    )
    (net (code "70") (name "unconnected-(U4-N.C.-Pad3)") (class "Default")
      (node (ref "U4") (pin "3") (pinfunction "N.C._3") (pintype "unspecified+no_connect"))
    )
    (net (code "71") (name "unconnected-(U5-DIO1-Pad6)") (class "Default")
      (node (ref "U5") (pin "6") (pinfunction "DIO1_6") (pintype "unspecified+no_connect"))
    )
    (net (code "72") (name "unconnected-(U5-DIO2-Pad7)") (class "Default")
      (node (ref "U5") (pin "7") (pinfunction "DIO2_7") (pintype "unspecified+no_connect"))
    )
    (net (code "73") (name "unconnected-(U5-DIO3-Pad8)") (class "Default")
      (node (ref "U5") (pin "8") (pinfunction "DIO3_8") (pintype "unspecified+no_connect"))
    )
    (net (code "74") (name "unconnected-(U5-DIO4-Pad10)") (class "Default")
      (node (ref "U5") (pin "10") (pinfunction "DIO4_10") (pintype "unspecified+no_connect"))
    )
    (net (code "75") (name "unconnected-(U5-DIO5-Pad11)") (class "Default")
      (node (ref "U5") (pin "11") (pinfunction "DIO5_11") (pintype "unspecified+no_connect"))
    )
    (net (code "76") (name "unconnected-(U8-BOOT_SEL-Pad8)") (class "Default")
      (node (ref "U8") (pin "8") (pinfunction "BOOT_SEL_8") (pintype "unspecified+no_connect"))
    )
    (net (code "77") (name "unconnected-(U8-GPIO3-Pad1)") (class "Default")
      (node (ref "U8") (pin "1") (pinfunction "GPIO3_1") (pintype "unspecified+no_connect"))
    )
    (net (code "78") (name "unconnected-(U8-GPIO4-Pad11)") (class "Default")
      (node (ref "U8") (pin "11") (pinfunction "GPIO4_11") (pintype "unspecified+no_connect"))
    )
    (net (code "79") (name "unconnected-(U8-GPIO5-Pad2)") (class "Default")
      (node (ref "U8") (pin "2") (pinfunction "GPIO5_2") (pintype "unspecified+no_connect"))
    )
    (net (code "80") (name "unconnected-(U8-GPIO28-Pad5)") (class "Default")
      (node (ref "U8") (pin "5") (pinfunction "GPIO28_5") (pintype "unspecified+no_connect"))
    )
    (net (code "81") (name "unconnected-(U8-GPIO29-Pad10)") (class "Default")
      (node (ref "U8") (pin "10") (pinfunction "GPIO29_10") (pintype "unspecified+no_connect"))
    )
    (net (code "82") (name "unconnected-(U8-GPIO30-Pad3)") (class "Default")
      (node (ref "U8") (pin "3") (pinfunction "GPIO30_3") (pintype "unspecified+no_connect"))
    )
    (net (code "83") (name "unconnected-(U8-GPIO31-Pad4)") (class "Default")
      (node (ref "U8") (pin "4") (pinfunction "GPIO31_4") (pintype "unspecified+no_connect"))
    )
    (net (code "84") (name "unconnected-(U9-3V0-Pad2)") (class "Default")
      (node (ref "U9") (pin "2") (pinfunction "3V0_2") (pintype "passive+no_connect"))
    )
    (net (code "85") (name "unconnected-(U9-CS-Pad7)") (class "Default")
      (node (ref "U9") (pin "7") (pinfunction "CS_7") (pintype "bidirectional+no_connect"))
    )
    (net (code "86") (name "unconnected-(U9-DO-Pad8)") (class "Default")
      (node (ref "U9") (pin "8") (pinfunction "DO_8") (pintype "bidirectional+no_connect"))
    )
    (net (code "87") (name "unconnected-(U9-DRDY-Pad9)") (class "Default")
      (node (ref "U9") (pin "9") (pinfunction "DRDY_9") (pintype "bidirectional+no_connect"))
    )
    (net (code "88") (name "unconnected-(U9-GND-Pad10)") (class "Default")
      (node (ref "U9") (pin "10") (pinfunction "GND_10") (pintype "passive+no_connect"))
    )
    (net (code "89") (name "unconnected-(U9-INT-Pad6)") (class "Default")
      (node (ref "U9") (pin "6") (pinfunction "INT_6") (pintype "bidirectional+no_connect"))
    )
    (net (code "90") (name "unconnected-(U17-DIO2-Pad6)") (class "Default")
      (node (ref "U17") (pin "6") (pinfunction "DIO2_6") (pintype "unspecified+no_connect"))
    )
    (net (code "91") (name "unconnected-(U17-DIO3-Pad7)") (class "Default")
      (node (ref "U17") (pin "7") (pinfunction "DIO3_7") (pintype "unspecified+no_connect"))
    )
    (net (code "92") (name "unconnected-(U19-+3.3V3-Pad55)") (class "Default")
      (node (ref "U19") (pin "55") (pinfunction "+3.3V3_55") (pintype "unspecified+no_connect"))
    )
    (net (code "93") (name "unconnected-(U19-+5V_host-Pad49)") (class "Default")
      (node (ref "U19") (pin "49") (pinfunction "+5V_host_49") (pintype "unspecified+no_connect"))
    )
    (net (code "94") (name "unconnected-(U19-G27-Pad19)") (class "Default")
      (node (ref "U19") (pin "19") (pinfunction "G27_19") (pintype "unspecified+no_connect"))
    )
    (net (code "95") (name "unconnected-(U19-G30-Pad22)") (class "Default")
      (node (ref "U19") (pin "22") (pinfunction "G30_22") (pintype "unspecified+no_connect"))
    )
    (net (code "96") (name "unconnected-(U19-G33-Pad25)") (class "Default")
      (node (ref "U19") (pin "25") (pinfunction "G33_25") (pintype "unspecified+no_connect"))
    )
    (net (code "97") (name "unconnected-(U19-G34-Pad26)") (class "Default")
      (node (ref "U19") (pin "26") (pinfunction "G34_26") (pintype "unspecified+no_connect"))
    )
    (net (code "98") (name "unconnected-(U19-PRGM-Pad57)") (class "Default")
      (node (ref "U19") (pin "57") (pinfunction "PRGM_57") (pintype "unspecified+no_connect"))
    )
    (net (code "99") (name "unconnected-(U22-VOUT-Pad9)") (class "Default")
      (node (ref "U22") (pin "9") (pinfunction "VOUT_9") (pintype "unspecified"))
    )
  )
)
